# DevBoard.net
KiCad netlist of a schematic drawn in EAGLE
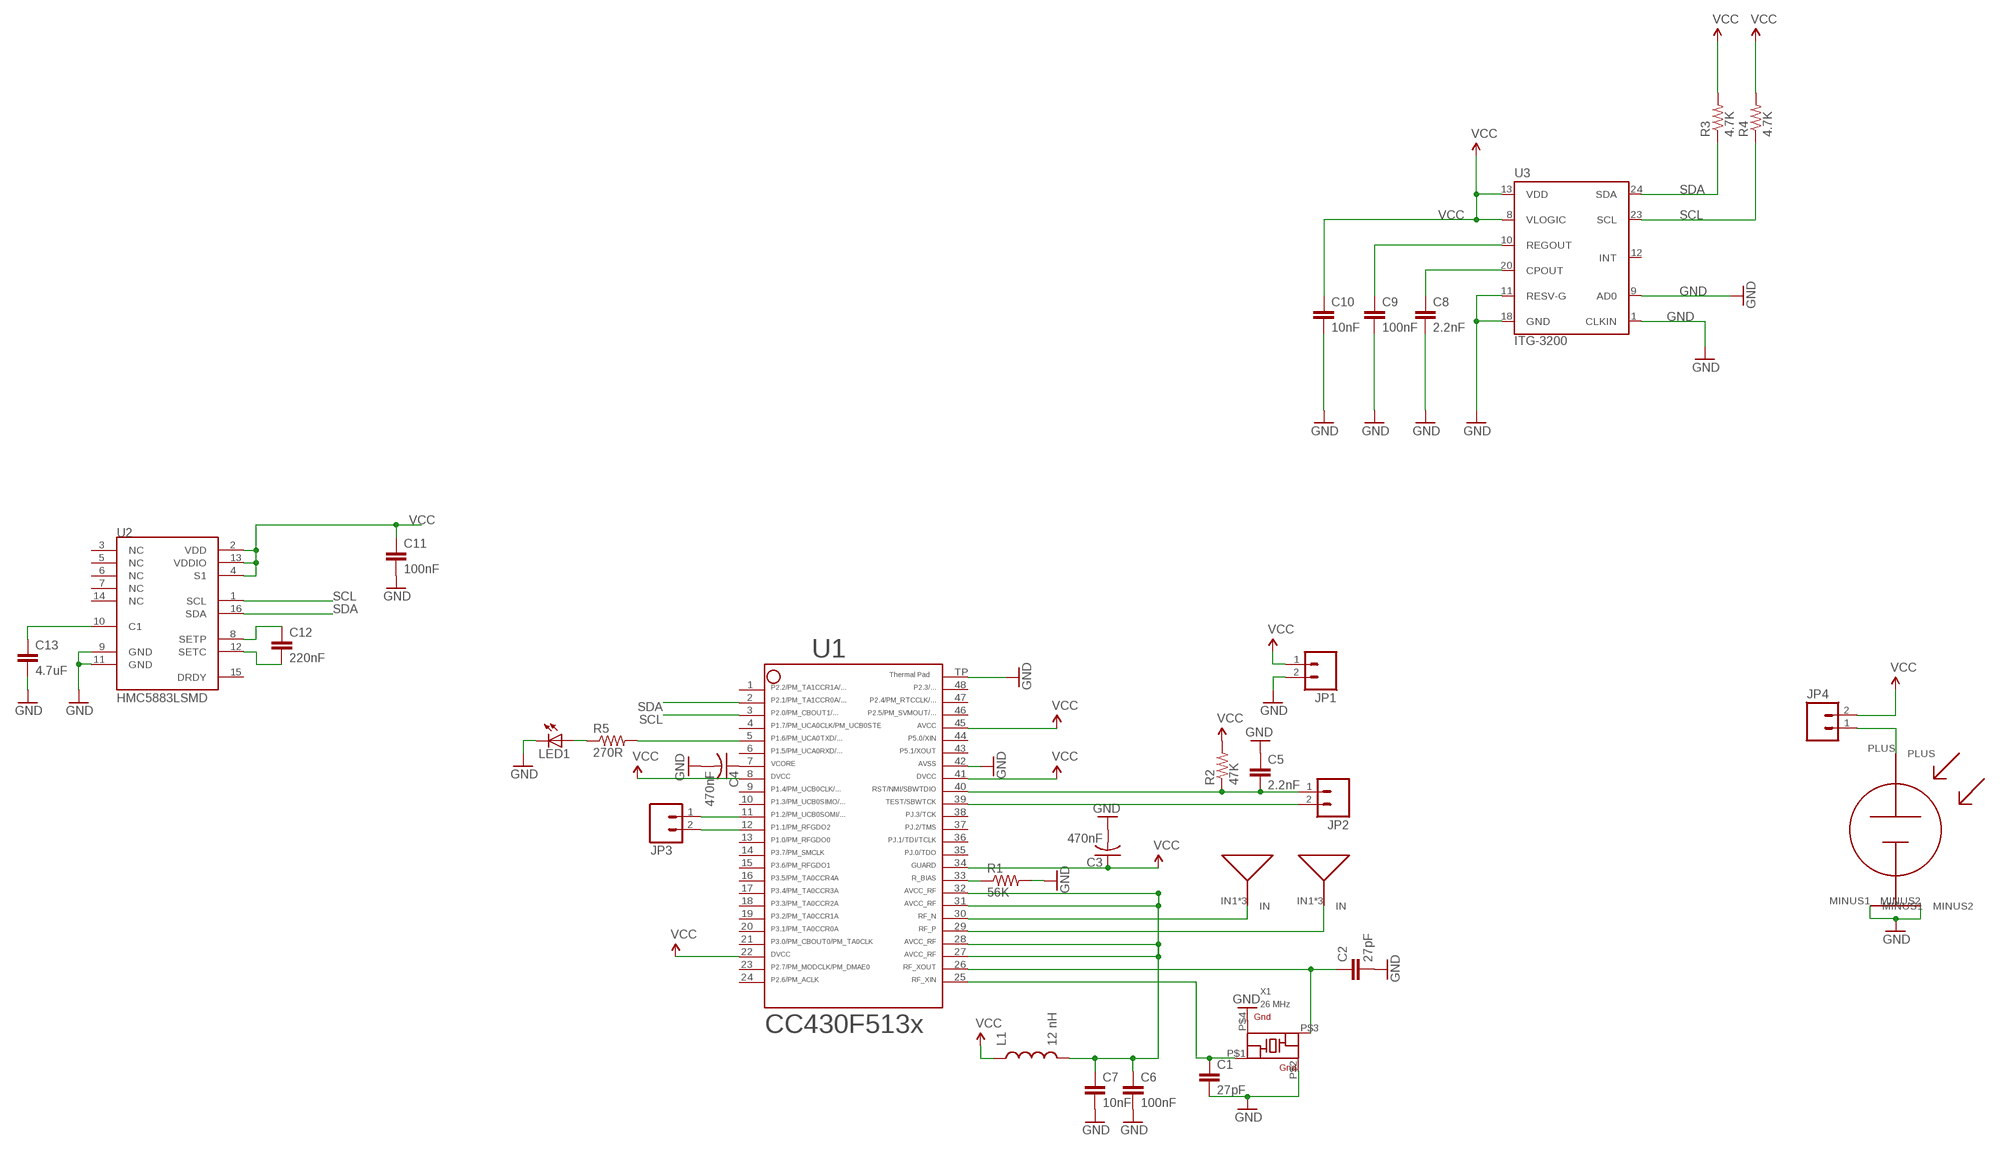
[diagram p0: schematic, sheet 1]

(export (version "E")
  (design (tool "Eeschema 10.0.6"))
  (components
    (comp (ref "ANT-N")
      (value "ANTENNA")
      (footprint "eagle-import:ANTENNA")
      (libsource (lib "eagle-import") (part "ANTENNA"))
    )
    (comp (ref "ANT-P")
      (value "ANTENNA")
      (footprint "eagle-import:ANTENNA")
      (libsource (lib "eagle-import") (part "ANTENNA"))
    )
    (comp (ref "C1")
      (value "27pF")
      (footprint "eagle-import:0603-CAP")
      (libsource (lib "eagle-import") (part "CAP0603-CAP"))
    )
    (comp (ref "C2")
      (value "27pF")
      (footprint "eagle-import:0603-CAP")
      (libsource (lib "eagle-import") (part "CAP0603-CAP"))
    )
    (comp (ref "C3")
      (value "470nF")
      (footprint "eagle-import:C0603")
      (libsource (lib "eagle-import") (part "C-USC0603"))
    )
    (comp (ref "C4")
      (value "470nF")
      (footprint "eagle-import:C0603")
      (libsource (lib "eagle-import") (part "C-USC0603"))
    )
    (comp (ref "C5")
      (value "2.2nF")
      (footprint "eagle-import:0603-CAP")
      (libsource (lib "eagle-import") (part "CAP0603-CAP"))
    )
    (comp (ref "C6")
      (value "100nF")
      (footprint "eagle-import:0603-CAP")
      (libsource (lib "eagle-import") (part "CAP0603-CAP"))
    )
    (comp (ref "C7")
      (value "10nF")
      (footprint "eagle-import:0603-CAP")
      (libsource (lib "eagle-import") (part "CAP0603-CAP"))
    )
    (comp (ref "C8")
      (value "2.2nF")
      (footprint "eagle-import:0603-CAP")
      (libsource (lib "eagle-import") (part "CAP0603-CAP"))
    )
    (comp (ref "C9")
      (value "100nF")
      (footprint "eagle-import:0603-CAP")
      (libsource (lib "eagle-import") (part "CAP0603-CAP"))
    )
    (comp (ref "C10")
      (value "10nF")
      (footprint "eagle-import:0603-CAP")
      (libsource (lib "eagle-import") (part "CAP0603-CAP"))
    )
    (comp (ref "C11")
      (value "100nF")
      (footprint "eagle-import:0603-CAP")
      (libsource (lib "eagle-import") (part "CAP0603-CAP"))
    )
    (comp (ref "C12")
      (value "220nF")
      (footprint "eagle-import:0603-CAP")
      (libsource (lib "eagle-import") (part "CAP0603-CAP"))
    )
    (comp (ref "C13")
      (value "4.7uF")
      (footprint "eagle-import:0603-CAP")
      (libsource (lib "eagle-import") (part "CAP0603-CAP"))
    )
    (comp (ref "JP1")
      (value "M02PTH")
      (footprint "eagle-import:1X02")
      (libsource (lib "eagle-import") (part "M02PTH"))
    )
    (comp (ref "JP2")
      (value "M02PTH")
      (footprint "eagle-import:1X02")
      (libsource (lib "eagle-import") (part "M02PTH"))
    )
    (comp (ref "JP3")
      (value "M02PTH")
      (footprint "eagle-import:1X02")
      (libsource (lib "eagle-import") (part "M02PTH"))
    )
    (comp (ref "JP4")
      (value "M02PTH")
      (footprint "eagle-import:1X02")
      (libsource (lib "eagle-import") (part "M02PTH"))
    )
    (comp (ref "L1")
      (value "12 nH")
      (footprint "eagle-import:0603")
      (libsource (lib "eagle-import") (part "INDUCTOR0603"))
    )
    (comp (ref "LED1")
      (value "LED0603")
      (footprint "eagle-import:LED-0603")
      (libsource (lib "eagle-import") (part "LED0603"))
    )
    (comp (ref "R1")
      (value "56K")
      (footprint "eagle-import:R0603")
      (libsource (lib "eagle-import") (part "R-US_R0603"))
    )
    (comp (ref "R2")
      (value "47K")
      (footprint "eagle-import:0603-RES")
      (libsource (lib "eagle-import") (part "RESISTOR0603-RES"))
    )
    (comp (ref "R3")
      (value "4.7K")
      (footprint "eagle-import:0603-RES")
      (libsource (lib "eagle-import") (part "RESISTOR0603-RES"))
    )
    (comp (ref "R4")
      (value "4.7K")
      (footprint "eagle-import:0603-RES")
      (libsource (lib "eagle-import") (part "RESISTOR0603-RES"))
    )
    (comp (ref "R5")
      (value "270R")
      (footprint "eagle-import:0603-RES")
      (libsource (lib "eagle-import") (part "RESISTOR0603-RES"))
    )
    (comp (ref "S1")
      (value "TASC")
      (footprint "eagle-import:TASC")
      (libsource (lib "eagle-import") (part "TASC"))
    )
    (comp (ref "U1")
      (value "CC430F5137")
      (footprint "eagle-import:RGZ48")
      (libsource (lib "eagle-import") (part "CC430F513X---RGZ48"))
    )
    (comp (ref "U2")
      (value "HMC5883LSMD")
      (footprint "eagle-import:16LPCC")
      (libsource (lib "eagle-import") (part "HMC5883LSMD"))
    )
    (comp (ref "U3")
      (value "ITG-3200")
      (footprint "eagle-import:QFN-24")
      (libsource (lib "eagle-import") (part "ITG-3200"))
    )
    (comp (ref "X1")
      (value "26 MHz")
      (footprint "eagle-import:ABM11_CERAMIC-SMD-CRYSTAL")
      (libsource (lib "eagle-import") (part "ABM11_CERAMIC_SMD_CRYSTALABM11"))
    )
  )
  (nets
    (net (code "1") (name "/SCL") (class "Default")
      (node (ref "R4") (pin "1") (pinfunction "1_1") (pintype "passive"))
      (node (ref "U1") (pin "3") (pinfunction "3_3") (pintype "bidirectional"))
      (node (ref "U2") (pin "1") (pinfunction "SCL_1") (pintype "bidirectional"))
      (node (ref "U3") (pin "23") (pinfunction "SCL_23") (pintype "bidirectional"))
    )
    (net (code "2") (name "/SDA") (class "Default")
      (node (ref "R3") (pin "1") (pinfunction "1_1") (pintype "passive"))
      (node (ref "U1") (pin "2") (pinfunction "2_2") (pintype "bidirectional"))
      (node (ref "U2") (pin "16") (pinfunction "SDA_16") (pintype "bidirectional"))
      (node (ref "U3") (pin "24") (pinfunction "SDA_24") (pintype "bidirectional"))
    )
    (net (code "3") (name "GND") (class "Default")
      (node (ref "C1") (pin "2") (pinfunction "2_2") (pintype "passive"))
      (node (ref "C10") (pin "2") (pinfunction "2_2") (pintype "passive"))
      (node (ref "C11") (pin "2") (pinfunction "2_2") (pintype "passive"))
      (node (ref "C13") (pin "2") (pinfunction "2_2") (pintype "passive"))
      (node (ref "C2") (pin "2") (pinfunction "2_2") (pintype "passive"))
      (node (ref "C3") (pin "2") (pinfunction "2_2") (pintype "passive"))
      (node (ref "C4") (pin "2") (pinfunction "2_2") (pintype "passive"))
      (node (ref "C5") (pin "1") (pinfunction "1_1") (pintype "passive"))
      (node (ref "C6") (pin "2") (pinfunction "2_2") (pintype "passive"))
      (node (ref "C7") (pin "2") (pinfunction "2_2") (pintype "passive"))
      (node (ref "C8") (pin "2") (pinfunction "2_2") (pintype "passive"))
      (node (ref "C9") (pin "2") (pinfunction "2_2") (pintype "passive"))
      (node (ref "JP1") (pin "2") (pinfunction "2_2") (pintype "passive"))
      (node (ref "LED1") (pin "C") (pinfunction "C_C") (pintype "passive"))
      (node (ref "R1") (pin "2") (pinfunction "2_2") (pintype "passive"))
      (node (ref "S1") (pin "MINUS1") (pinfunction "MINUS1_MINUS1") (pintype "power_in"))
      (node (ref "S1") (pin "MINUS2") (pinfunction "MINUS2_MINUS2") (pintype "power_in"))
      (node (ref "U1") (pin "42") (pinfunction "42_42") (pintype "power_in"))
      (node (ref "U1") (pin "TP") (pinfunction "49_TP") (pintype "power_in"))
      (node (ref "U2") (pin "11") (pinfunction "GND_11") (pintype "bidirectional"))
      (node (ref "U2") (pin "9") (pinfunction "GND_9") (pintype "bidirectional"))
      (node (ref "U3") (pin "1") (pinfunction "CLKIN_1") (pintype "bidirectional"))
      (node (ref "U3") (pin "11") (pinfunction "RESV-G_11") (pintype "bidirectional"))
      (node (ref "U3") (pin "18") (pinfunction "GND_18") (pintype "bidirectional"))
      (node (ref "U3") (pin "9") (pinfunction "AD0_9") (pintype "bidirectional"))
      (node (ref "X1") (pin "P$2") (pinfunction "GROUND2_P$2") (pintype "bidirectional"))
      (node (ref "X1") (pin "P$4") (pinfunction "GROUND4_P$4") (pintype "bidirectional"))
    )
    (net (code "4") (name "Net-(ANT-N-IN-PadIN1)") (class "Default")
      (node (ref "ANT-N") (pin "IN1") (pinfunction "IN_IN1") (pintype "bidirectional"))
      (node (ref "ANT-N") (pin "IN2") (pinfunction "IN_IN2") (pintype "bidirectional"))
      (node (ref "ANT-N") (pin "IN3") (pinfunction "IN_IN3") (pintype "bidirectional"))
      (node (ref "U1") (pin "30") (pinfunction "30_30") (pintype "bidirectional"))
    )
    (net (code "5") (name "Net-(ANT-P-IN-PadIN1)") (class "Default")
      (node (ref "ANT-P") (pin "IN1") (pinfunction "IN_IN1") (pintype "bidirectional"))
      (node (ref "ANT-P") (pin "IN2") (pinfunction "IN_IN2") (pintype "bidirectional"))
      (node (ref "ANT-P") (pin "IN3") (pinfunction "IN_IN3") (pintype "bidirectional"))
      (node (ref "U1") (pin "29") (pinfunction "29_29") (pintype "bidirectional"))
    )
    (net (code "6") (name "Net-(C1-Pad1)") (class "Default")
      (node (ref "C1") (pin "1") (pinfunction "1_1") (pintype "passive"))
      (node (ref "U1") (pin "25") (pinfunction "25_25") (pintype "input"))
      (node (ref "X1") (pin "P$1") (pinfunction "P$1_P$1") (pintype "bidirectional"))
    )
    (net (code "7") (name "Net-(C2-Pad1)") (class "Default")
      (node (ref "C2") (pin "1") (pinfunction "1_1") (pintype "passive"))
      (node (ref "U1") (pin "26") (pinfunction "26_26") (pintype "output"))
      (node (ref "X1") (pin "P$3") (pinfunction "P$3_P$3") (pintype "bidirectional"))
    )
    (net (code "8") (name "Net-(C4-Pad1)") (class "Default")
      (node (ref "C4") (pin "1") (pinfunction "1_1") (pintype "passive"))
      (node (ref "U1") (pin "7") (pinfunction "7_7") (pintype "power_in"))
    )
    (net (code "9") (name "Net-(C5-Pad2)") (class "Default")
      (node (ref "C5") (pin "2") (pinfunction "2_2") (pintype "passive"))
      (node (ref "JP2") (pin "1") (pinfunction "1_1") (pintype "passive"))
      (node (ref "R2") (pin "1") (pinfunction "1_1") (pintype "passive"))
      (node (ref "U1") (pin "40") (pinfunction "40_40") (pintype "bidirectional"))
    )
    (net (code "10") (name "Net-(C6-Pad1)") (class "Default")
      (node (ref "C6") (pin "1") (pinfunction "1_1") (pintype "passive"))
      (node (ref "C7") (pin "1") (pinfunction "1_1") (pintype "passive"))
      (node (ref "L1") (pin "2") (pinfunction "2_2") (pintype "passive"))
      (node (ref "U1") (pin "27") (pinfunction "27_27") (pintype "power_in"))
      (node (ref "U1") (pin "28") (pinfunction "28_28") (pintype "bidirectional"))
      (node (ref "U1") (pin "31") (pinfunction "31_31") (pintype "power_in"))
      (node (ref "U1") (pin "32") (pinfunction "32_32") (pintype "power_in"))
    )
    (net (code "11") (name "Net-(JP2-Pad2)") (class "Default")
      (node (ref "JP2") (pin "2") (pinfunction "2_2") (pintype "passive"))
      (node (ref "U1") (pin "39") (pinfunction "39_39") (pintype "input"))
    )
    (net (code "12") (name "Net-(JP3-Pad1)") (class "Default")
      (node (ref "JP3") (pin "1") (pinfunction "1_1") (pintype "passive"))
      (node (ref "U1") (pin "11") (pinfunction "11_11") (pintype "bidirectional"))
    )
    (net (code "13") (name "Net-(JP3-Pad2)") (class "Default")
      (node (ref "JP3") (pin "2") (pinfunction "2_2") (pintype "passive"))
      (node (ref "U1") (pin "12") (pinfunction "12_12") (pintype "bidirectional"))
    )
    (net (code "14") (name "Net-(JP4-Pad1)") (class "Default")
      (node (ref "JP4") (pin "1") (pinfunction "1_1") (pintype "passive"))
      (node (ref "S1") (pin "PLUS") (pinfunction "PLUS_PLUS") (pintype "power_in"))
    )
    (net (code "15") (name "Net-(LED1-PadA)") (class "Default")
      (node (ref "LED1") (pin "A") (pinfunction "A_A") (pintype "passive"))
      (node (ref "R5") (pin "1") (pinfunction "1_1") (pintype "passive"))
    )
    (net (code "16") (name "Net-(R1-Pad1)") (class "Default")
      (node (ref "R1") (pin "1") (pinfunction "1_1") (pintype "passive"))
      (node (ref "U1") (pin "33") (pinfunction "33_33") (pintype "power_in"))
    )
    (net (code "17") (name "Net-(R5-Pad2)") (class "Default")
      (node (ref "R5") (pin "2") (pinfunction "2_2") (pintype "passive"))
      (node (ref "U1") (pin "5") (pinfunction "5_5") (pintype "bidirectional"))
    )
    (net (code "18") (name "Net-(U2-C1)") (class "Default")
      (node (ref "C13") (pin "1") (pinfunction "1_1") (pintype "passive"))
      (node (ref "U2") (pin "10") (pinfunction "C1_10") (pintype "bidirectional"))
    )
    (net (code "19") (name "Net-(U2-SETC)") (class "Default")
      (node (ref "C12") (pin "2") (pinfunction "2_2") (pintype "passive"))
      (node (ref "U2") (pin "12") (pinfunction "SETC_12") (pintype "bidirectional"))
    )
    (net (code "20") (name "Net-(U2-SETP)") (class "Default")
      (node (ref "C12") (pin "1") (pinfunction "1_1") (pintype "passive"))
      (node (ref "U2") (pin "8") (pinfunction "SETP_8") (pintype "bidirectional"))
    )
    (net (code "21") (name "Net-(U3-CPOUT)") (class "Default")
      (node (ref "C8") (pin "1") (pinfunction "1_1") (pintype "passive"))
      (node (ref "U3") (pin "20") (pinfunction "CPOUT_20") (pintype "bidirectional"))
    )
    (net (code "22") (name "Net-(U3-REGOUT)") (class "Default")
      (node (ref "C9") (pin "1") (pinfunction "1_1") (pintype "passive"))
      (node (ref "U3") (pin "10") (pinfunction "REGOUT_10") (pintype "bidirectional"))
    )
    (net (code "23") (name "VCC") (class "Default")
      (node (ref "C10") (pin "1") (pinfunction "1_1") (pintype "passive"))
      (node (ref "C11") (pin "1") (pinfunction "1_1") (pintype "passive"))
      (node (ref "C3") (pin "1") (pinfunction "1_1") (pintype "passive"))
      (node (ref "JP1") (pin "1") (pinfunction "1_1") (pintype "passive"))
      (node (ref "JP4") (pin "2") (pinfunction "2_2") (pintype "passive"))
      (node (ref "L1") (pin "1") (pinfunction "1_1") (pintype "passive"))
      (node (ref "R2") (pin "2") (pinfunction "2_2") (pintype "passive"))
      (node (ref "R3") (pin "2") (pinfunction "2_2") (pintype "passive"))
      (node (ref "R4") (pin "2") (pinfunction "2_2") (pintype "passive"))
      (node (ref "U1") (pin "22") (pinfunction "22_22") (pintype "power_in"))
      (node (ref "U1") (pin "34") (pinfunction "34_34") (pintype "power_in"))
      (node (ref "U1") (pin "41") (pinfunction "41_41") (pintype "power_in"))
      (node (ref "U1") (pin "45") (pinfunction "45_45") (pintype "input"))
      (node (ref "U1") (pin "8") (pinfunction "8_8") (pintype "power_in"))
      (node (ref "U2") (pin "13") (pinfunction "VDDIO_13") (pintype "bidirectional"))
      (node (ref "U2") (pin "2") (pinfunction "VDD_2") (pintype "bidirectional"))
      (node (ref "U2") (pin "4") (pinfunction "S1_4") (pintype "bidirectional"))
      (node (ref "U3") (pin "13") (pinfunction "VDD_13") (pintype "bidirectional"))
      (node (ref "U3") (pin "8") (pinfunction "VLOGIC_8") (pintype "bidirectional"))
    )
    (net (code "24") (name "unconnected-(U1-Pad1)") (class "Default")
      (node (ref "U1") (pin "1") (pinfunction "1_1") (pintype "bidirectional"))
    )
    (net (code "25") (name "unconnected-(U1-Pad4)") (class "Default")
      (node (ref "U1") (pin "4") (pinfunction "4_4") (pintype "bidirectional"))
    )
    (net (code "26") (name "unconnected-(U1-Pad6)") (class "Default")
      (node (ref "U1") (pin "6") (pinfunction "6_6") (pintype "bidirectional"))
    )
    (net (code "27") (name "unconnected-(U1-Pad9)") (class "Default")
      (node (ref "U1") (pin "9") (pinfunction "9_9") (pintype "bidirectional"))
    )
    (net (code "28") (name "unconnected-(U1-Pad10)") (class "Default")
      (node (ref "U1") (pin "10") (pinfunction "10_10") (pintype "bidirectional"))
    )
    (net (code "29") (name "unconnected-(U1-Pad13)") (class "Default")
      (node (ref "U1") (pin "13") (pinfunction "13_13") (pintype "bidirectional"))
    )
    (net (code "30") (name "unconnected-(U1-Pad14)") (class "Default")
      (node (ref "U1") (pin "14") (pinfunction "14_14") (pintype "bidirectional"))
    )
    (net (code "31") (name "unconnected-(U1-Pad15)") (class "Default")
      (node (ref "U1") (pin "15") (pinfunction "15_15") (pintype "bidirectional"))
    )
    (net (code "32") (name "unconnected-(U1-Pad16)") (class "Default")
      (node (ref "U1") (pin "16") (pinfunction "16_16") (pintype "bidirectional"))
    )
    (net (code "33") (name "unconnected-(U1-Pad17)") (class "Default")
      (node (ref "U1") (pin "17") (pinfunction "17_17") (pintype "bidirectional"))
    )
    (net (code "34") (name "unconnected-(U1-Pad18)") (class "Default")
      (node (ref "U1") (pin "18") (pinfunction "18_18") (pintype "bidirectional"))
    )
    (net (code "35") (name "unconnected-(U1-Pad19)") (class "Default")
      (node (ref "U1") (pin "19") (pinfunction "19_19") (pintype "bidirectional"))
    )
    (net (code "36") (name "unconnected-(U1-Pad20)") (class "Default")
      (node (ref "U1") (pin "20") (pinfunction "20_20") (pintype "bidirectional"))
    )
    (net (code "37") (name "unconnected-(U1-Pad21)") (class "Default")
      (node (ref "U1") (pin "21") (pinfunction "21_21") (pintype "bidirectional"))
    )
    (net (code "38") (name "unconnected-(U1-Pad23)") (class "Default")
      (node (ref "U1") (pin "23") (pinfunction "23_23") (pintype "bidirectional"))
    )
    (net (code "39") (name "unconnected-(U1-Pad24)") (class "Default")
      (node (ref "U1") (pin "24") (pinfunction "24_24") (pintype "bidirectional"))
    )
    (net (code "40") (name "unconnected-(U1-Pad35)") (class "Default")
      (node (ref "U1") (pin "35") (pinfunction "35_35") (pintype "bidirectional"))
    )
    (net (code "41") (name "unconnected-(U1-Pad36)") (class "Default")
      (node (ref "U1") (pin "36") (pinfunction "36_36") (pintype "bidirectional"))
    )
    (net (code "42") (name "unconnected-(U1-Pad37)") (class "Default")
      (node (ref "U1") (pin "37") (pinfunction "37_37") (pintype "bidirectional"))
    )
    (net (code "43") (name "unconnected-(U1-Pad38)") (class "Default")
      (node (ref "U1") (pin "38") (pinfunction "38_38") (pintype "bidirectional"))
    )
    (net (code "44") (name "unconnected-(U1-Pad43)") (class "Default")
      (node (ref "U1") (pin "43") (pinfunction "43_43") (pintype "input"))
    )
    (net (code "45") (name "unconnected-(U1-Pad44)") (class "Default")
      (node (ref "U1") (pin "44") (pinfunction "44_44") (pintype "input"))
    )
    (net (code "46") (name "unconnected-(U1-Pad46)") (class "Default")
      (node (ref "U1") (pin "46") (pinfunction "46_46") (pintype "bidirectional"))
    )
    (net (code "47") (name "unconnected-(U1-Pad47)") (class "Default")
      (node (ref "U1") (pin "47") (pinfunction "47_47") (pintype "input"))
    )
    (net (code "48") (name "unconnected-(U1-Pad48)") (class "Default")
      (node (ref "U1") (pin "48") (pinfunction "48_48") (pintype "bidirectional"))
    )
    (net (code "49") (name "unconnected-(U2-DRDY-Pad15)") (class "Default")
      (node (ref "U2") (pin "15") (pinfunction "DRDY_15") (pintype "bidirectional"))
    )
    (net (code "50") (name "unconnected-(U2-NC-Pad3)") (class "Default")
      (node (ref "U2") (pin "3") (pinfunction "NC_3") (pintype "bidirectional"))
    )
    (net (code "51") (name "unconnected-(U2-NC-Pad5)") (class "Default")
      (node (ref "U2") (pin "5") (pinfunction "NC_5") (pintype "bidirectional"))
    )
    (net (code "52") (name "unconnected-(U2-NC-Pad6)") (class "Default")
      (node (ref "U2") (pin "6") (pinfunction "NC_6") (pintype "bidirectional"))
    )
    (net (code "53") (name "unconnected-(U2-NC-Pad7)") (class "Default")
      (node (ref "U2") (pin "7") (pinfunction "NC_7") (pintype "bidirectional"))
    )
    (net (code "54") (name "unconnected-(U2-NC-Pad14)") (class "Default")
      (node (ref "U2") (pin "14") (pinfunction "NC_14") (pintype "bidirectional"))
    )
    (net (code "55") (name "unconnected-(U3-INT-Pad12)") (class "Default")
      (node (ref "U3") (pin "12") (pinfunction "INT_12") (pintype "bidirectional"))
    )
  )
)
